# FTDI_USB_To_UART.net
KiCad netlist of a schematic drawn in Altium Designer
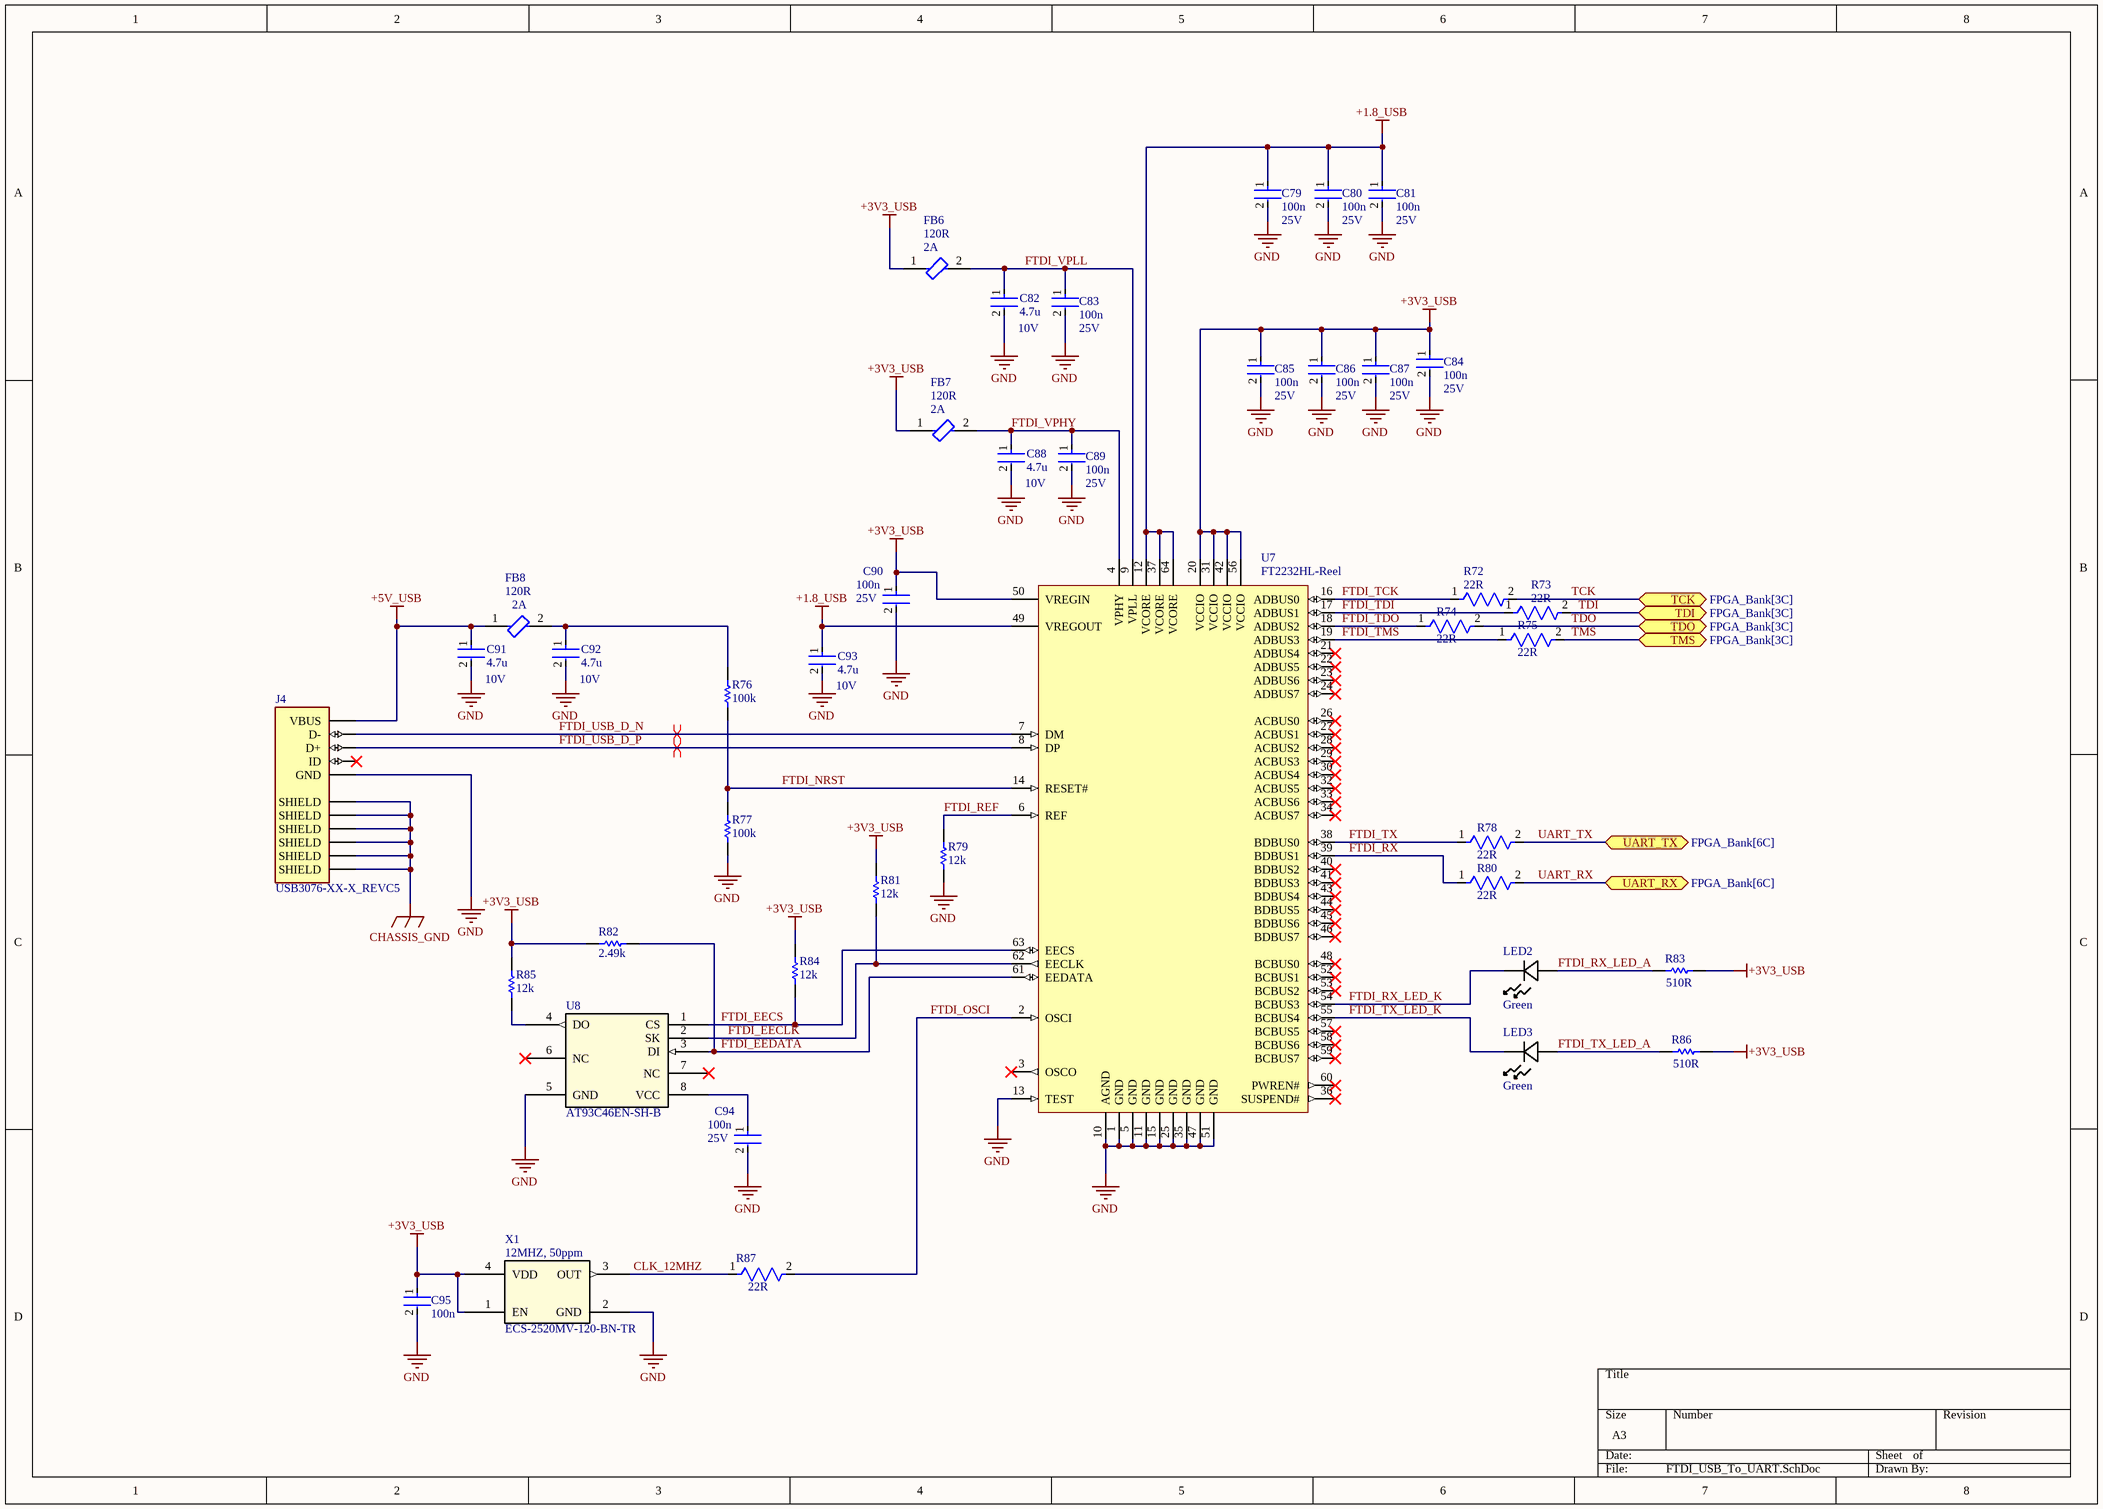
[diagram p0: FTDI_USB_To_UART.SchDoc]

(export (version "E")
  (design (tool "Eeschema 10.0.6"))
  (components
    (comp (ref "C79")
      (value "100n")
      (footprint "FP-CL278-IPC_C")
      (description "Cap Ceramic 100nF 25V X5R ±10% SMD 0402 +85°C Paper T/R")
      (fields (field (name "VOLTAGE") "25V") (field (name "TOLERANCE") "10%"))
      (libsource (lib "Altium Content Vault") (part "b4654b650e69147ec39a6b967a45e02"))
    )
    (comp (ref "C80")
      (value "100n")
      (footprint "FP-CL278-IPC_C")
      (description "Cap Ceramic 100nF 25V X5R ±10% SMD 0402 +85°C Paper T/R")
      (fields (field (name "VOLTAGE") "25V") (field (name "TOLERANCE") "10%"))
      (libsource (lib "Altium Content Vault") (part "b4654b650e69147ec39a6b967a45e02"))
    )
    (comp (ref "C81")
      (value "100n")
      (footprint "FP-CL278-IPC_C")
      (description "Cap Ceramic 100nF 25V X5R ±10% SMD 0402 +85°C Paper T/R")
      (fields (field (name "VOLTAGE") "25V") (field (name "TOLERANCE") "10%"))
      (libsource (lib "Altium Content Vault") (part "b4654b650e69147ec39a6b967a45e02"))
    )
    (comp (ref "C82")
      (value "4.7u")
      (footprint "FP-CL282-IPC_C")
      (description "Cap Ceramic 4.7uF 10V X5R ±20% SMD 0402 +85°C Paper T/R")
      (fields (field (name "TOLERANCE") "20%"))
      (libsource (lib "Altium Content Vault") (part "b4654b650e69147ec39a6b967a45e02"))
    )
    (comp (ref "C83")
      (value "100n")
      (footprint "FP-CL278-IPC_C")
      (description "Cap Ceramic 100nF 25V X5R ±10% SMD 0402 +85°C Paper T/R")
      (fields (field (name "VOLTAGE") "25V") (field (name "TOLERANCE") "10%"))
      (libsource (lib "Altium Content Vault") (part "b4654b650e69147ec39a6b967a45e02"))
    )
    (comp (ref "C84")
      (value "100n")
      (footprint "FP-CL278-IPC_C")
      (description "Cap Ceramic 100nF 25V X5R ±10% SMD 0402 +85°C Paper T/R")
      (fields (field (name "VOLTAGE") "25V") (field (name "TOLERANCE") "10%"))
      (libsource (lib "Altium Content Vault") (part "b4654b650e69147ec39a6b967a45e02"))
    )
    (comp (ref "C85")
      (value "100n")
      (footprint "FP-CL278-IPC_C")
      (description "Cap Ceramic 100nF 25V X5R ±10% SMD 0402 +85°C Paper T/R")
      (fields (field (name "VOLTAGE") "25V") (field (name "TOLERANCE") "10%"))
      (libsource (lib "Altium Content Vault") (part "b4654b650e69147ec39a6b967a45e02"))
    )
    (comp (ref "C86")
      (value "100n")
      (footprint "FP-CL278-IPC_C")
      (description "Cap Ceramic 100nF 25V X5R ±10% SMD 0402 +85°C Paper T/R")
      (fields (field (name "VOLTAGE") "25V") (field (name "TOLERANCE") "10%"))
      (libsource (lib "Altium Content Vault") (part "b4654b650e69147ec39a6b967a45e02"))
    )
    (comp (ref "C87")
      (value "100n")
      (footprint "FP-CL278-IPC_C")
      (description "Cap Ceramic 100nF 25V X5R ±10% SMD 0402 +85°C Paper T/R")
      (fields (field (name "VOLTAGE") "25V") (field (name "TOLERANCE") "10%"))
      (libsource (lib "Altium Content Vault") (part "b4654b650e69147ec39a6b967a45e02"))
    )
    (comp (ref "C88")
      (value "4.7u")
      (footprint "FP-CL282-IPC_C")
      (description "Cap Ceramic 4.7uF 10V X5R ±20% SMD 0402 +85°C Paper T/R")
      (fields (field (name "TOLERANCE") "20%"))
      (libsource (lib "Altium Content Vault") (part "b4654b650e69147ec39a6b967a45e02"))
    )
    (comp (ref "C89")
      (value "100n")
      (footprint "FP-CL278-IPC_C")
      (description "Cap Ceramic 100nF 25V X5R ±10% SMD 0402 +85°C Paper T/R")
      (fields (field (name "VOLTAGE") "25V") (field (name "TOLERANCE") "10%"))
      (libsource (lib "Altium Content Vault") (part "b4654b650e69147ec39a6b967a45e02"))
    )
    (comp (ref "C90")
      (value "100n")
      (footprint "FP-CL278-IPC_C")
      (description "Cap Ceramic 100nF 25V X5R ±10% SMD 0402 +85°C Paper T/R")
      (fields (field (name "VOLTAGE") "25V") (field (name "TOLERANCE") "10%"))
      (libsource (lib "Altium Content Vault") (part "b4654b650e69147ec39a6b967a45e02"))
    )
    (comp (ref "C91")
      (value "4.7u")
      (footprint "FP-CL282-IPC_C")
      (description "Cap Ceramic 4.7uF 10V X5R ±20% SMD 0402 +85°C Paper T/R")
      (fields (field (name "TOLERANCE") "20%"))
      (libsource (lib "Altium Content Vault") (part "b4654b650e69147ec39a6b967a45e02"))
    )
    (comp (ref "C92")
      (value "4.7u")
      (footprint "FP-CL282-IPC_C")
      (description "Cap Ceramic 4.7uF 10V X5R ±20% SMD 0402 +85°C Paper T/R")
      (fields (field (name "TOLERANCE") "20%"))
      (libsource (lib "Altium Content Vault") (part "b4654b650e69147ec39a6b967a45e02"))
    )
    (comp (ref "C93")
      (value "4.7u")
      (footprint "FP-CL282-IPC_C")
      (description "Cap Ceramic 4.7uF 10V X5R ±20% SMD 0402 +85°C Paper T/R")
      (fields (field (name "TOLERANCE") "20%"))
      (libsource (lib "Altium Content Vault") (part "b4654b650e69147ec39a6b967a45e02"))
    )
    (comp (ref "C94")
      (value "100n")
      (footprint "FP-CL278-IPC_C")
      (description "Cap Ceramic 100nF 25V X5R ±10% SMD 0402 +85°C Paper T/R")
      (fields (field (name "VOLTAGE") "25V") (field (name "TOLERANCE") "10%"))
      (libsource (lib "Altium Content Vault") (part "b4654b650e69147ec39a6b967a45e02"))
    )
    (comp (ref "C95")
      (value "100n")
      (footprint "FP-CL278-IPC_C")
      (description "Cap Ceramic 100nF 25V X5R ±10% SMD 0402 +85°C Paper T/R")
      (fields (field (name "VOLTAGE") "25V") (field (name "TOLERANCE") "10%"))
      (libsource (lib "Altium Content Vault") (part "b4654b650e69147ec39a6b967a45e02"))
    )
    (comp (ref "FB6")
      (value "120R")
      (footprint "FP-BLM15-0_05-d0_7-MFG")
      (description "Chip Ferrite Bead, 0402, 120Ω @ 100MHz, 0.055Ω, 25%, 2A")
      (fields (field (name "TOLERANCE") "25%"))
      (libsource (lib "Altium Content Vault") (part "5f30dd21d616792df468990f7003faa"))
    )
    (comp (ref "FB7")
      (value "120R")
      (footprint "FP-BLM15-0_05-d0_7-MFG")
      (description "Chip Ferrite Bead, 0402, 120Ω @ 100MHz, 0.055Ω, 25%, 2A")
      (fields (field (name "TOLERANCE") "25%"))
      (libsource (lib "Altium Content Vault") (part "5f30dd21d616792df468990f7003faa"))
    )
    (comp (ref "FB8")
      (value "120R")
      (footprint "FP-BLM15-0_05-d0_7-MFG")
      (description "Chip Ferrite Bead, 0402, 120Ω @ 100MHz, 0.055Ω, 25%, 2A")
      (fields (field (name "TOLERANCE") "25%"))
      (libsource (lib "Altium Content Vault") (part "5f30dd21d616792df468990f7003faa"))
    )
    (comp (ref "J4")
      (value "USB3076-XX-X_REVC5")
      (footprint "GCT_USB3076-XX-X_REVC5")
      (fields (field (name "MP") "USB3076-30-A") (field (name "MF") "Global Connector Technology"))
      (libsource (lib "SerDes_Eval") (part "USB3076-XX-X_REVC5"))
    )
    (comp (ref "LED2")
      (value "Green")
      (footprint "LED_LTW-C193TS5_LTO")
      (description "No Description Available")
      (fields
        (field (name "MANUFACTURER_PART_NUMBER") "LTST-C191TGKT")
        (field (name "COPYRIGHT") "Copyright (C) 2025 Ultra Librarian. All rights reserved.")
      )
      (libsource (lib "SerDes_Eval") (part "LTST-C191TGKT"))
    )
    (comp (ref "LED3")
      (value "Green")
      (footprint "LED_LTW-C193TS5_LTO")
      (description "No Description Available")
      (fields
        (field (name "MANUFACTURER_PART_NUMBER") "LTST-C191TGKT")
        (field (name "COPYRIGHT") "Copyright (C) 2025 Ultra Librarian. All rights reserved.")
      )
      (libsource (lib "SerDes_Eval") (part "LTST-C191TGKT"))
    )
    (comp (ref "R72")
      (value "22R")
      (footprint "FP-RC0402-0_4-MFG")
      (fields (field (name "TOLERANCE") "1%"))
      (libsource (lib "Altium Content Vault") (part "RC0402FR-0722RL"))
    )
    (comp (ref "R73")
      (value "22R")
      (footprint "FP-RC0402-0_4-MFG")
      (fields (field (name "TOLERANCE") "1%"))
      (libsource (lib "Altium Content Vault") (part "RC0402FR-0722RL"))
    )
    (comp (ref "R74")
      (value "22R")
      (footprint "FP-RC0402-0_4-MFG")
      (fields (field (name "TOLERANCE") "1%"))
      (libsource (lib "Altium Content Vault") (part "RC0402FR-0722RL"))
    )
    (comp (ref "R75")
      (value "22R")
      (footprint "FP-RC0402-0_4-MFG")
      (fields (field (name "TOLERANCE") "1%"))
      (libsource (lib "Altium Content Vault") (part "RC0402FR-0722RL"))
    )
    (comp (ref "R76")
      (value "100k")
      (footprint "RESC1005X40X25NL05T10")
      (fields (field (name "PART NUMBER") "RC0402FR-07100KL") (field (name "MANUFACTURER") "Yageo / Phycomp"))
      (libsource (lib "Altium Content Vault") (part "RES"))
    )
    (comp (ref "R77")
      (value "100k")
      (footprint "RESC1005X40X25NL05T10")
      (fields (field (name "PART NUMBER") "RC0402FR-07100KL") (field (name "MANUFACTURER") "Yageo / Phycomp"))
      (libsource (lib "Altium Content Vault") (part "RES"))
    )
    (comp (ref "R78")
      (value "22R")
      (footprint "FP-RC0402-0_4-MFG")
      (fields (field (name "TOLERANCE") "1%"))
      (libsource (lib "Altium Content Vault") (part "RC0402FR-0722RL"))
    )
    (comp (ref "R79")
      (value "12k")
      (footprint "RESC1005X40X25NL05T10")
      (fields (field (name "PART NUMBER") "RC0402FR-07100KL") (field (name "MANUFACTURER") "Yageo / Phycomp"))
      (libsource (lib "Altium Content Vault") (part "RES"))
    )
    (comp (ref "R80")
      (value "22R")
      (footprint "FP-RC0402-0_4-MFG")
      (fields (field (name "TOLERANCE") "1%"))
      (libsource (lib "Altium Content Vault") (part "RC0402FR-0722RL"))
    )
    (comp (ref "R81")
      (value "12k")
      (footprint "RESC1005X40X25NL05T10")
      (fields (field (name "PART NUMBER") "RC0402FR-07100KL") (field (name "MANUFACTURER") "Yageo / Phycomp"))
      (libsource (lib "Altium Content Vault") (part "RES"))
    )
    (comp (ref "R82")
      (value "2.49k")
      (footprint "RESC1005X40X25NL05T10")
      (fields (field (name "PART NUMBER") "RC0402FR-072K49L") (field (name "MANUFACTURER") "Yageo"))
      (libsource (lib "Altium Content Vault") (part "RES"))
    )
    (comp (ref "R83")
      (value "510R")
      (footprint "RESC1005X40X25LL05T05")
      (fields (field (name "PART NUMBER") "CRCW0402510RFKED") (field (name "MANUFACTURER") "Vishay Dale"))
      (libsource (lib "Altium Content Vault") (part "RES"))
    )
    (comp (ref "R84")
      (value "12k")
      (footprint "RESC1005X40X25NL05T10")
      (fields (field (name "PART NUMBER") "RC0402FR-07100KL") (field (name "MANUFACTURER") "Yageo / Phycomp"))
      (libsource (lib "Altium Content Vault") (part "RES"))
    )
    (comp (ref "R85")
      (value "12k")
      (footprint "RESC1005X40X25NL05T10")
      (fields (field (name "PART NUMBER") "RC0402FR-07100KL") (field (name "MANUFACTURER") "Yageo / Phycomp"))
      (libsource (lib "Altium Content Vault") (part "RES"))
    )
    (comp (ref "R86")
      (value "510R")
      (footprint "RESC1005X40X25LL05T05")
      (fields (field (name "PART NUMBER") "CRCW0402510RFKED") (field (name "MANUFACTURER") "Vishay Dale"))
      (libsource (lib "Altium Content Vault") (part "RES"))
    )
    (comp (ref "R87")
      (value "22R")
      (footprint "FP-RC0402-0_4-MFG")
      (fields (field (name "TOLERANCE") "1%"))
      (libsource (lib "Altium Content Vault") (part "RC0402FR-0722RL"))
    )
    (comp (ref "U7")
      (value "FT2232HL-Reel")
      (footprint "LQFP-64_M")
      (description "Dual High Speed USB To Multipurpose UART/FIFO IC, 64-pin LQFP, Tape and Reel")
      (fields (field (name "MANUFACTURER") "FTDI"))
      (libsource (lib "Altium Content Vault") (part "COM-UART-FT2232H-LQFP64"))
    )
    (comp (ref "U8")
      (value "AT93C46EN-SH-B")
      (footprint "8S1_ATM")
      (description "No Description Available")
      (fields (field (name "COPYRIGHT") "Copyright (C) 2025 Ultra Librarian. All rights reserved."))
      (libsource (lib "SerDes_Eval") (part "AT93C46EN-SH-B"))
    )
    (comp (ref "X1")
      (value "ECS-2520MV-120-BN-TR")
      (footprint "SMD4_ECS-2520MV_ECS")
      (description "Description")
      (fields (field (name "COPYRIGHT") "Copyright (C) 2025 Ultra Librarian. All rights reserved."))
      (libsource (lib "SerDes_Eval") (part "ECS-2520MV-120-BN-TR"))
    )
  )
  (nets
    (net (code "1") (name "+1.8_USB") (class "Default")
      (node (ref "C79") (pin "1") (pinfunction "1_1") (pintype "passive"))
      (node (ref "C80") (pin "1") (pinfunction "1_1") (pintype "passive"))
      (node (ref "C81") (pin "1") (pinfunction "1_1") (pintype "passive"))
      (node (ref "C93") (pin "1") (pinfunction "1_1") (pintype "passive"))
      (node (ref "U7") (pin "12") (pinfunction "VCORE_12") (pintype "power_in"))
      (node (ref "U7") (pin "37") (pinfunction "VCORE_37") (pintype "power_in"))
      (node (ref "U7") (pin "49") (pinfunction "VREGOUT_49") (pintype "power_in"))
      (node (ref "U7") (pin "64") (pinfunction "VCORE_64") (pintype "power_in"))
    )
    (net (code "2") (name "+3V3_USB") (class "Default")
      (node (ref "C84") (pin "1") (pinfunction "1_1") (pintype "passive"))
      (node (ref "C85") (pin "1") (pinfunction "1_1") (pintype "passive"))
      (node (ref "C86") (pin "1") (pinfunction "1_1") (pintype "passive"))
      (node (ref "C87") (pin "1") (pinfunction "1_1") (pintype "passive"))
      (node (ref "C90") (pin "1") (pinfunction "1_1") (pintype "passive"))
      (node (ref "C95") (pin "1") (pinfunction "1_1") (pintype "passive"))
      (node (ref "FB6") (pin "1") (pinfunction "1_1") (pintype "passive"))
      (node (ref "FB7") (pin "1") (pinfunction "1_1") (pintype "passive"))
      (node (ref "R81") (pin "2") (pinfunction "2_2") (pintype "passive"))
      (node (ref "R82") (pin "1") (pinfunction "1_1") (pintype "passive"))
      (node (ref "R83") (pin "2") (pinfunction "2_2") (pintype "passive"))
      (node (ref "R84") (pin "2") (pinfunction "2_2") (pintype "passive"))
      (node (ref "R85") (pin "2") (pinfunction "2_2") (pintype "passive"))
      (node (ref "R86") (pin "2") (pinfunction "2_2") (pintype "passive"))
      (node (ref "U7") (pin "20") (pinfunction "VCCIO_20") (pintype "power_in"))
      (node (ref "U7") (pin "31") (pinfunction "VCCIO_31") (pintype "power_in"))
      (node (ref "U7") (pin "42") (pinfunction "VCCIO_42") (pintype "power_in"))
      (node (ref "U7") (pin "50") (pinfunction "VREGIN_50") (pintype "power_in"))
      (node (ref "U7") (pin "56") (pinfunction "VCCIO_56") (pintype "power_in"))
      (node (ref "X1") (pin "1") (pinfunction "EN_1") (pintype "passive"))
      (node (ref "X1") (pin "4") (pinfunction "VDD_4") (pintype "power_in"))
    )
    (net (code "3") (name "+5V_USB") (class "Default")
      (node (ref "C91") (pin "1") (pinfunction "1_1") (pintype "passive"))
      (node (ref "FB8") (pin "1") (pinfunction "1_1") (pintype "passive"))
      (node (ref "J4") (pin "1") (pinfunction "VBUS_1") (pintype "power_in"))
    )
    (net (code "4") (name "/CLK_12MHZ") (class "Default")
      (node (ref "R87") (pin "1") (pinfunction "1_1") (pintype "passive"))
      (node (ref "X1") (pin "3") (pinfunction "OUT_3") (pintype "output"))
    )
    (net (code "5") (name "/FTDI_EECLK") (class "Default")
      (node (ref "R81") (pin "1") (pinfunction "1_1") (pintype "passive"))
      (node (ref "U7") (pin "62") (pinfunction "EECLK_62") (pintype "output"))
      (node (ref "U8") (pin "2") (pinfunction "SK_2") (pintype "passive"))
    )
    (net (code "6") (name "/FTDI_EECS") (class "Default")
      (node (ref "R84") (pin "1") (pinfunction "1_1") (pintype "passive"))
      (node (ref "U7") (pin "63") (pinfunction "EECS_63") (pintype "bidirectional"))
      (node (ref "U8") (pin "1") (pinfunction "CS_1") (pintype "passive"))
    )
    (net (code "7") (name "/FTDI_EEDATA") (class "Default")
      (node (ref "R82") (pin "2") (pinfunction "2_2") (pintype "passive"))
      (node (ref "U7") (pin "61") (pinfunction "EEDATA_61") (pintype "bidirectional"))
      (node (ref "U8") (pin "3") (pinfunction "DI_3") (pintype "input"))
    )
    (net (code "8") (name "/FTDI_NRST") (class "Default")
      (node (ref "R76") (pin "1") (pinfunction "1_1") (pintype "passive"))
      (node (ref "R77") (pin "2") (pinfunction "2_2") (pintype "passive"))
      (node (ref "U7") (pin "14") (pinfunction "RESET#_14") (pintype "input"))
    )
    (net (code "9") (name "/FTDI_OSCI") (class "Default")
      (node (ref "R87") (pin "2") (pinfunction "2_2") (pintype "passive"))
      (node (ref "U7") (pin "2") (pinfunction "OSCI_2") (pintype "input"))
    )
    (net (code "10") (name "/FTDI_REF") (class "Default")
      (node (ref "R79") (pin "2") (pinfunction "2_2") (pintype "passive"))
      (node (ref "U7") (pin "6") (pinfunction "REF_6") (pintype "input"))
    )
    (net (code "11") (name "/FTDI_RX") (class "Default")
      (node (ref "R80") (pin "1") (pinfunction "1_1") (pintype "passive"))
      (node (ref "U7") (pin "39") (pinfunction "BDBUS1_39") (pintype "bidirectional"))
    )
    (net (code "12") (name "/FTDI_RX_LED_A") (class "Default")
      (node (ref "LED2") (pin "2") (pinfunction "2_2") (pintype "passive"))
      (node (ref "R83") (pin "1") (pinfunction "1_1") (pintype "passive"))
    )
    (net (code "13") (name "/FTDI_RX_LED_K") (class "Default")
      (node (ref "LED2") (pin "1") (pinfunction "1_1") (pintype "passive"))
      (node (ref "U7") (pin "54") (pinfunction "BCBUS3_54") (pintype "bidirectional"))
    )
    (net (code "14") (name "/FTDI_TCK") (class "Default")
      (node (ref "R72") (pin "1") (pinfunction "1_1") (pintype "passive"))
      (node (ref "U7") (pin "16") (pinfunction "ADBUS0_16") (pintype "bidirectional"))
    )
    (net (code "15") (name "/FTDI_TDI") (class "Default")
      (node (ref "R73") (pin "1") (pinfunction "1_1") (pintype "passive"))
      (node (ref "U7") (pin "17") (pinfunction "ADBUS1_17") (pintype "bidirectional"))
    )
    (net (code "16") (name "/FTDI_TDO") (class "Default")
      (node (ref "R74") (pin "1") (pinfunction "1_1") (pintype "passive"))
      (node (ref "U7") (pin "18") (pinfunction "ADBUS2_18") (pintype "bidirectional"))
    )
    (net (code "17") (name "/FTDI_TMS") (class "Default")
      (node (ref "R75") (pin "1") (pinfunction "1_1") (pintype "passive"))
      (node (ref "U7") (pin "19") (pinfunction "ADBUS3_19") (pintype "bidirectional"))
    )
    (net (code "18") (name "/FTDI_TX") (class "Default")
      (node (ref "R78") (pin "1") (pinfunction "1_1") (pintype "passive"))
      (node (ref "U7") (pin "38") (pinfunction "BDBUS0_38") (pintype "bidirectional"))
    )
    (net (code "19") (name "/FTDI_TX_LED_A") (class "Default")
      (node (ref "LED3") (pin "2") (pinfunction "2_2") (pintype "passive"))
      (node (ref "R86") (pin "1") (pinfunction "1_1") (pintype "passive"))
    )
    (net (code "20") (name "/FTDI_TX_LED_K") (class "Default")
      (node (ref "LED3") (pin "1") (pinfunction "1_1") (pintype "passive"))
      (node (ref "U7") (pin "55") (pinfunction "BCBUS4_55") (pintype "bidirectional"))
    )
    (net (code "21") (name "/FTDI_USB_D_N") (class "Default")
      (node (ref "J4") (pin "2") (pinfunction "D-_2") (pintype "bidirectional"))
      (node (ref "U7") (pin "7") (pinfunction "DM_7") (pintype "input"))
    )
    (net (code "22") (name "/FTDI_USB_D_P") (class "Default")
      (node (ref "J4") (pin "3") (pinfunction "D+_3") (pintype "bidirectional"))
      (node (ref "U7") (pin "8") (pinfunction "DP_8") (pintype "input"))
    )
    (net (code "23") (name "/FTDI_VPHY") (class "Default")
      (node (ref "C88") (pin "1") (pinfunction "1_1") (pintype "passive"))
      (node (ref "C89") (pin "1") (pinfunction "1_1") (pintype "passive"))
      (node (ref "FB7") (pin "2") (pinfunction "2_2") (pintype "passive"))
      (node (ref "U7") (pin "4") (pinfunction "VPHY_4") (pintype "power_in"))
    )
    (net (code "24") (name "/FTDI_VPLL") (class "Default")
      (node (ref "C82") (pin "1") (pinfunction "1_1") (pintype "passive"))
      (node (ref "C83") (pin "1") (pinfunction "1_1") (pintype "passive"))
      (node (ref "FB6") (pin "2") (pinfunction "2_2") (pintype "passive"))
      (node (ref "U7") (pin "9") (pinfunction "VPLL_9") (pintype "power_in"))
    )
    (net (code "25") (name "/TCK") (class "Default")
      (node (ref "R72") (pin "2") (pinfunction "2_2") (pintype "passive"))
    )
    (net (code "26") (name "/TDI") (class "Default")
      (node (ref "R73") (pin "2") (pinfunction "2_2") (pintype "passive"))
    )
    (net (code "27") (name "/TDO") (class "Default")
      (node (ref "R74") (pin "2") (pinfunction "2_2") (pintype "passive"))
    )
    (net (code "28") (name "/TMS") (class "Default")
      (node (ref "R75") (pin "2") (pinfunction "2_2") (pintype "passive"))
    )
    (net (code "29") (name "/UART_RX") (class "Default")
      (node (ref "R80") (pin "2") (pinfunction "2_2") (pintype "passive"))
    )
    (net (code "30") (name "/UART_TX") (class "Default")
      (node (ref "R78") (pin "2") (pinfunction "2_2") (pintype "passive"))
    )
    (net (code "31") (name "CHASSIS_GND") (class "Default")
      (node (ref "J4") (pin "10") (pinfunction "SHIELD_10") (pintype "power_in"))
      (node (ref "J4") (pin "11") (pinfunction "SHIELD_11") (pintype "power_in"))
      (node (ref "J4") (pin "6") (pinfunction "SHIELD_6") (pintype "power_in"))
      (node (ref "J4") (pin "7") (pinfunction "SHIELD_7") (pintype "power_in"))
      (node (ref "J4") (pin "8") (pinfunction "SHIELD_8") (pintype "power_in"))
      (node (ref "J4") (pin "9") (pinfunction "SHIELD_9") (pintype "power_in"))
    )
    (net (code "32") (name "GND") (class "Default")
      (node (ref "C79") (pin "2") (pinfunction "2_2") (pintype "passive"))
      (node (ref "C80") (pin "2") (pinfunction "2_2") (pintype "passive"))
      (node (ref "C81") (pin "2") (pinfunction "2_2") (pintype "passive"))
      (node (ref "C82") (pin "2") (pinfunction "2_2") (pintype "passive"))
      (node (ref "C83") (pin "2") (pinfunction "2_2") (pintype "passive"))
      (node (ref "C84") (pin "2") (pinfunction "2_2") (pintype "passive"))
      (node (ref "C85") (pin "2") (pinfunction "2_2") (pintype "passive"))
      (node (ref "C86") (pin "2") (pinfunction "2_2") (pintype "passive"))
      (node (ref "C87") (pin "2") (pinfunction "2_2") (pintype "passive"))
      (node (ref "C88") (pin "2") (pinfunction "2_2") (pintype "passive"))
      (node (ref "C89") (pin "2") (pinfunction "2_2") (pintype "passive"))
      (node (ref "C90") (pin "2") (pinfunction "2_2") (pintype "passive"))
      (node (ref "C91") (pin "2") (pinfunction "2_2") (pintype "passive"))
      (node (ref "C92") (pin "2") (pinfunction "2_2") (pintype "passive"))
      (node (ref "C93") (pin "2") (pinfunction "2_2") (pintype "passive"))
      (node (ref "C94") (pin "2") (pinfunction "2_2") (pintype "passive"))
      (node (ref "C95") (pin "2") (pinfunction "2_2") (pintype "passive"))
      (node (ref "J4") (pin "5") (pinfunction "GND_5") (pintype "power_in"))
      (node (ref "R77") (pin "1") (pinfunction "1_1") (pintype "passive"))
      (node (ref "R79") (pin "1") (pinfunction "1_1") (pintype "passive"))
      (node (ref "U7") (pin "1") (pinfunction "GND_1") (pintype "power_in"))
      (node (ref "U7") (pin "10") (pinfunction "AGND_10") (pintype "power_in"))
      (node (ref "U7") (pin "11") (pinfunction "GND_11") (pintype "power_in"))
      (node (ref "U7") (pin "13") (pinfunction "TEST_13") (pintype "input"))
      (node (ref "U7") (pin "15") (pinfunction "GND_15") (pintype "power_in"))
      (node (ref "U7") (pin "25") (pinfunction "GND_25") (pintype "power_in"))
      (node (ref "U7") (pin "35") (pinfunction "GND_35") (pintype "power_in"))
      (node (ref "U7") (pin "47") (pinfunction "GND_47") (pintype "power_in"))
      (node (ref "U7") (pin "5") (pinfunction "GND_5") (pintype "power_in"))
      (node (ref "U7") (pin "51") (pinfunction "GND_51") (pintype "power_in"))
      (node (ref "U8") (pin "5") (pinfunction "GND_5") (pintype "power_in"))
      (node (ref "X1") (pin "2") (pinfunction "GND_2") (pintype "power_in"))
    )
    (net (code "33") (name "Net-(C92-Pad1)") (class "Default")
      (node (ref "C92") (pin "1") (pinfunction "1_1") (pintype "passive"))
      (node (ref "FB8") (pin "2") (pinfunction "2_2") (pintype "passive"))
      (node (ref "R76") (pin "2") (pinfunction "2_2") (pintype "passive"))
    )
    (net (code "34") (name "Net-(U8-DO)") (class "Default")
      (node (ref "R85") (pin "1") (pinfunction "1_1") (pintype "passive"))
      (node (ref "U8") (pin "4") (pinfunction "DO_4") (pintype "output"))
    )
    (net (code "35") (name "Net-(U8-VCC)") (class "Default")
      (node (ref "C94") (pin "1") (pinfunction "1_1") (pintype "passive"))
      (node (ref "U8") (pin "8") (pinfunction "VCC_8") (pintype "power_in"))
    )
    (net (code "36") (name "unconnected-(J4-ID-Pad4)") (class "Default")
      (node (ref "J4") (pin "4") (pinfunction "ID_4") (pintype "bidirectional+no_connect"))
    )
    (net (code "37") (name "unconnected-(U7-ACBUS0-Pad26)") (class "Default")
      (node (ref "U7") (pin "26") (pinfunction "ACBUS0_26") (pintype "bidirectional+no_connect"))
    )
    (net (code "38") (name "unconnected-(U7-ACBUS1-Pad27)") (class "Default")
      (node (ref "U7") (pin "27") (pinfunction "ACBUS1_27") (pintype "bidirectional+no_connect"))
    )
    (net (code "39") (name "unconnected-(U7-ACBUS2-Pad28)") (class "Default")
      (node (ref "U7") (pin "28") (pinfunction "ACBUS2_28") (pintype "bidirectional+no_connect"))
    )
    (net (code "40") (name "unconnected-(U7-ACBUS3-Pad29)") (class "Default")
      (node (ref "U7") (pin "29") (pinfunction "ACBUS3_29") (pintype "bidirectional+no_connect"))
    )
    (net (code "41") (name "unconnected-(U7-ACBUS4-Pad30)") (class "Default")
      (node (ref "U7") (pin "30") (pinfunction "ACBUS4_30") (pintype "bidirectional+no_connect"))
    )
    (net (code "42") (name "unconnected-(U7-ACBUS5-Pad32)") (class "Default")
      (node (ref "U7") (pin "32") (pinfunction "ACBUS5_32") (pintype "bidirectional+no_connect"))
    )
    (net (code "43") (name "unconnected-(U7-ACBUS6-Pad33)") (class "Default")
      (node (ref "U7") (pin "33") (pinfunction "ACBUS6_33") (pintype "bidirectional+no_connect"))
    )
    (net (code "44") (name "unconnected-(U7-ACBUS7-Pad34)") (class "Default")
      (node (ref "U7") (pin "34") (pinfunction "ACBUS7_34") (pintype "bidirectional+no_connect"))
    )
    (net (code "45") (name "unconnected-(U7-ADBUS4-Pad21)") (class "Default")
      (node (ref "U7") (pin "21") (pinfunction "ADBUS4_21") (pintype "bidirectional+no_connect"))
    )
    (net (code "46") (name "unconnected-(U7-ADBUS5-Pad22)") (class "Default")
      (node (ref "U7") (pin "22") (pinfunction "ADBUS5_22") (pintype "bidirectional+no_connect"))
    )
    (net (code "47") (name "unconnected-(U7-ADBUS6-Pad23)") (class "Default")
      (node (ref "U7") (pin "23") (pinfunction "ADBUS6_23") (pintype "bidirectional+no_connect"))
    )
    (net (code "48") (name "unconnected-(U7-ADBUS7-Pad24)") (class "Default")
      (node (ref "U7") (pin "24") (pinfunction "ADBUS7_24") (pintype "bidirectional+no_connect"))
    )
    (net (code "49") (name "unconnected-(U7-BCBUS0-Pad48)") (class "Default")
      (node (ref "U7") (pin "48") (pinfunction "BCBUS0_48") (pintype "bidirectional+no_connect"))
    )
    (net (code "50") (name "unconnected-(U7-BCBUS1-Pad52)") (class "Default")
      (node (ref "U7") (pin "52") (pinfunction "BCBUS1_52") (pintype "bidirectional+no_connect"))
    )
    (net (code "51") (name "unconnected-(U7-BCBUS2-Pad53)") (class "Default")
      (node (ref "U7") (pin "53") (pinfunction "BCBUS2_53") (pintype "bidirectional+no_connect"))
    )
    (net (code "52") (name "unconnected-(U7-BCBUS5-Pad57)") (class "Default")
      (node (ref "U7") (pin "57") (pinfunction "BCBUS5_57") (pintype "bidirectional+no_connect"))
    )
    (net (code "53") (name "unconnected-(U7-BCBUS6-Pad58)") (class "Default")
      (node (ref "U7") (pin "58") (pinfunction "BCBUS6_58") (pintype "bidirectional+no_connect"))
    )
    (net (code "54") (name "unconnected-(U7-BCBUS7-Pad59)") (class "Default")
      (node (ref "U7") (pin "59") (pinfunction "BCBUS7_59") (pintype "bidirectional+no_connect"))
    )
    (net (code "55") (name "unconnected-(U7-BDBUS2-Pad40)") (class "Default")
      (node (ref "U7") (pin "40") (pinfunction "BDBUS2_40") (pintype "bidirectional+no_connect"))
    )
    (net (code "56") (name "unconnected-(U7-BDBUS3-Pad41)") (class "Default")
      (node (ref "U7") (pin "41") (pinfunction "BDBUS3_41") (pintype "bidirectional+no_connect"))
    )
    (net (code "57") (name "unconnected-(U7-BDBUS4-Pad43)") (class "Default")
      (node (ref "U7") (pin "43") (pinfunction "BDBUS4_43") (pintype "bidirectional+no_connect"))
    )
    (net (code "58") (name "unconnected-(U7-BDBUS5-Pad44)") (class "Default")
      (node (ref "U7") (pin "44") (pinfunction "BDBUS5_44") (pintype "bidirectional+no_connect"))
    )
    (net (code "59") (name "unconnected-(U7-BDBUS6-Pad45)") (class "Default")
      (node (ref "U7") (pin "45") (pinfunction "BDBUS6_45") (pintype "bidirectional+no_connect"))
    )
    (net (code "60") (name "unconnected-(U7-BDBUS7-Pad46)") (class "Default")
      (node (ref "U7") (pin "46") (pinfunction "BDBUS7_46") (pintype "bidirectional+no_connect"))
    )
    (net (code "61") (name "unconnected-(U7-OSCO-Pad3)") (class "Default")
      (node (ref "U7") (pin "3") (pinfunction "OSCO_3") (pintype "output+no_connect"))
    )
    (net (code "62") (name "unconnected-(U7-PWREN#-Pad60)") (class "Default")
      (node (ref "U7") (pin "60") (pinfunction "PWREN#_60") (pintype "output+no_connect"))
    )
    (net (code "63") (name "unconnected-(U7-SUSPEND#-Pad36)") (class "Default")
      (node (ref "U7") (pin "36") (pinfunction "SUSPEND#_36") (pintype "output+no_connect"))
    )
    (net (code "64") (name "unconnected-(U8-NC-Pad6)") (class "Default")
      (node (ref "U8") (pin "6") (pinfunction "NC_6") (pintype "passive+no_connect"))
    )
    (net (code "65") (name "unconnected-(U8-NC-Pad7)") (class "Default")
      (node (ref "U8") (pin "7") (pinfunction "NC_7") (pintype "passive+no_connect"))
    )
  )
)
